# hcgs-servo-slam.net
KiCad netlist of a schematic drawn in EAGLE
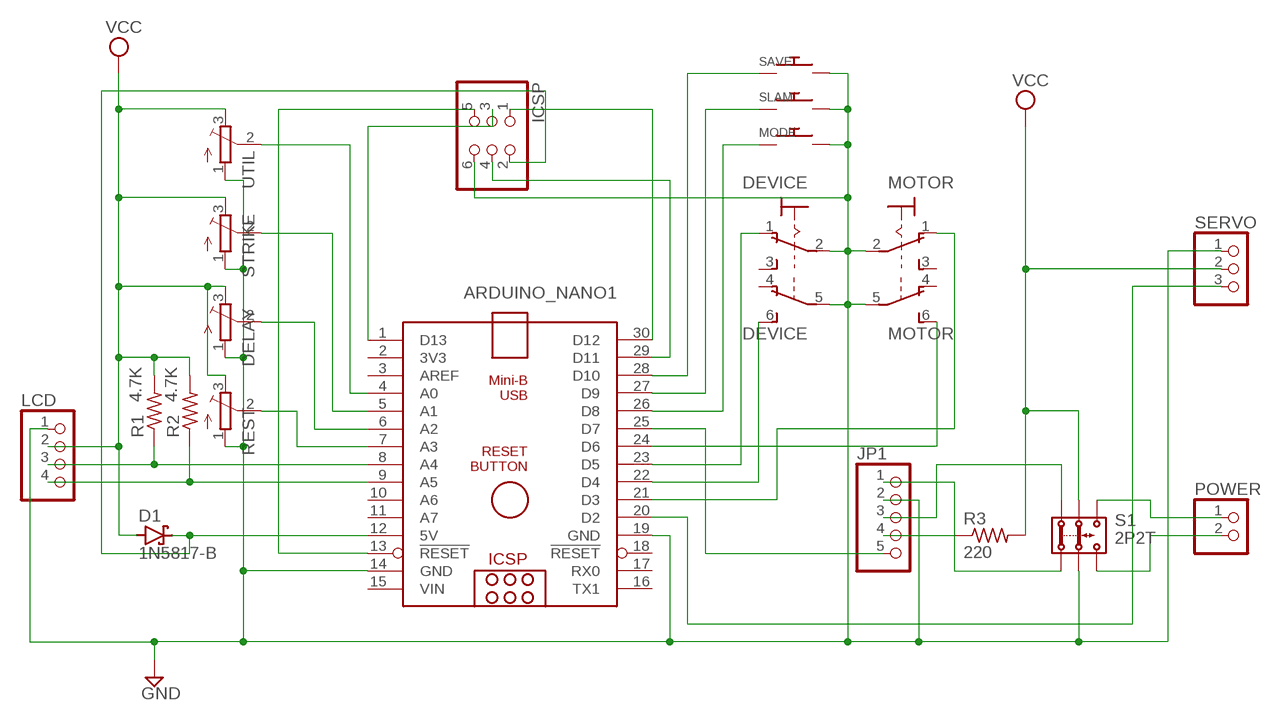
[diagram p0: schematic, sheet 1]

(export (version "E")
  (design (tool "Eeschema 10.0.6"))
  (components
    (comp (ref "ARDUINO_NANO1")
      (value "ARDUINO_NANO_HCARDUINO_NANO_NO_HOLE")
      (footprint "eagle-import:ARDUINO_NANO_NO_HOLE")
      (libsource (lib "eagle-import") (part "ARDUINO_NANO_HCARDUINO_NANO_NO_HOLE"))
    )
    (comp (ref "D1")
      (value "1N5817-B")
      (footprint "eagle-import:DO41-7.6")
      (libsource (lib "eagle-import") (part "1N5817-B"))
    )
    (comp (ref "DELAY")
      (value "TRIMPOT3386")
      (footprint "eagle-import:TRIM-3386")
      (libsource (lib "eagle-import") (part "TRIMPOT3386"))
    )
    (comp (ref "DEVICE")
      (value "320-938")
      (footprint "eagle-import:320-938")
      (libsource (lib "eagle-import") (part "320-938"))
    )
    (comp (ref "ICSP")
      (value "PINHD-2X3")
      (footprint "eagle-import:2X03")
      (libsource (lib "eagle-import") (part "PINHD-2X3"))
    )
    (comp (ref "JP1")
      (value "PINHD-1X5")
      (footprint "eagle-import:1X05")
      (libsource (lib "eagle-import") (part "PINHD-1X5"))
    )
    (comp (ref "LCD")
      (value "PINHD-1X4")
      (footprint "eagle-import:1X04")
      (libsource (lib "eagle-import") (part "PINHD-1X4"))
    )
    (comp (ref "MODE")
      (value "SWITCH_PUSHBUTTONEVQ-PE")
      (footprint "eagle-import:TACT_PANA-EVQ")
      (libsource (lib "eagle-import") (part "SWITCH_PUSHBUTTONEVQ-PE"))
    )
    (comp (ref "MOTOR")
      (value "320-938")
      (footprint "eagle-import:320-938")
      (libsource (lib "eagle-import") (part "320-938"))
    )
    (comp (ref "POWER")
      (value "PINHD-1X2")
      (footprint "eagle-import:1X02")
      (libsource (lib "eagle-import") (part "PINHD-1X2"))
    )
    (comp (ref "R1")
      (value "4.7K")
      (footprint "eagle-import:0309_12")
      (libsource (lib "eagle-import") (part "R-US_0309/12"))
    )
    (comp (ref "R2")
      (value "4.7K")
      (footprint "eagle-import:0309_12")
      (libsource (lib "eagle-import") (part "R-US_0309/12"))
    )
    (comp (ref "R3")
      (value "220")
      (footprint "eagle-import:0309_12")
      (libsource (lib "eagle-import") (part "R-US_0309/12"))
    )
    (comp (ref "REST")
      (value "TRIMPOT3386")
      (footprint "eagle-import:TRIM-3386")
      (libsource (lib "eagle-import") (part "TRIMPOT3386"))
    )
    (comp (ref "S1")
      (value "2P2T")
      (footprint "eagle-import:2P2T")
      (libsource (lib "eagle-import") (part "2P2T"))
    )
    (comp (ref "SAVE")
      (value "SWITCH_PUSHBUTTONEVQ-PE")
      (footprint "eagle-import:TACT_PANA-EVQ")
      (libsource (lib "eagle-import") (part "SWITCH_PUSHBUTTONEVQ-PE"))
    )
    (comp (ref "SERVO")
      (value "PINHD-1X3")
      (footprint "eagle-import:1X03")
      (libsource (lib "eagle-import") (part "PINHD-1X3"))
    )
    (comp (ref "SLAM")
      (value "SWITCH_PUSHBUTTONEVQ-PE")
      (footprint "eagle-import:TACT_PANA-EVQ")
      (libsource (lib "eagle-import") (part "SWITCH_PUSHBUTTONEVQ-PE"))
    )
    (comp (ref "STRIKE")
      (value "TRIMPOT3386")
      (footprint "eagle-import:TRIM-3386")
      (libsource (lib "eagle-import") (part "TRIMPOT3386"))
    )
    (comp (ref "UTIL")
      (value "TRIMPOT3386")
      (footprint "eagle-import:TRIM-3386")
      (libsource (lib "eagle-import") (part "TRIMPOT3386"))
    )
  )
  (nets
    (net (code "1") (name "/VIN") (class "Default")
      (node (ref "ARDUINO_NANO1") (pin "15") (pinfunction "VIN_15") (pintype "power_in"))
    )
    (net (code "2") (name "GND") (class "Default")
      (node (ref "ARDUINO_NANO1") (pin "14") (pinfunction "GND_14") (pintype "power_in"))
      (node (ref "ARDUINO_NANO1") (pin "19") (pinfunction "GND_19") (pintype "power_in"))
      (node (ref "DELAY") (pin "1") (pinfunction "A_1") (pintype "passive"))
      (node (ref "DEVICE") (pin "2") (pinfunction "P_2") (pintype "passive"))
      (node (ref "DEVICE") (pin "5") (pinfunction "P_5") (pintype "passive"))
      (node (ref "ICSP") (pin "6") (pinfunction "6_6") (pintype "passive"))
      (node (ref "JP1") (pin "2") (pinfunction "2_2") (pintype "passive"))
      (node (ref "LCD") (pin "1") (pinfunction "1_1") (pintype "passive"))
      (node (ref "MODE") (pin "P$2") (pinfunction "P$2_P$2") (pintype "passive"))
      (node (ref "MOTOR") (pin "2") (pinfunction "P_2") (pintype "passive"))
      (node (ref "MOTOR") (pin "5") (pinfunction "P_5") (pintype "passive"))
      (node (ref "REST") (pin "1") (pinfunction "A_1") (pintype "passive"))
      (node (ref "S1") (pin "2.2") (pinfunction "2.2_2.2") (pintype "passive"))
      (node (ref "SAVE") (pin "P$2") (pinfunction "P$2_P$2") (pintype "passive"))
      (node (ref "SERVO") (pin "1") (pinfunction "1_1") (pintype "passive"))
      (node (ref "SLAM") (pin "P$2") (pinfunction "P$2_P$2") (pintype "passive"))
      (node (ref "STRIKE") (pin "1") (pinfunction "A_1") (pintype "passive"))
      (node (ref "UTIL") (pin "1") (pinfunction "A_1") (pintype "passive"))
    )
    (net (code "3") (name "Net-(ARDUINO_NANO1-5V)") (class "Default")
      (node (ref "ARDUINO_NANO1") (pin "12") (pinfunction "5V_12") (pintype "power_in"))
      (node (ref "D1") (pin "C") (pinfunction "C_C") (pintype "passive"))
      (node (ref "ICSP") (pin "2") (pinfunction "2_2") (pintype "passive"))
    )
    (net (code "4") (name "Net-(ARDUINO_NANO1-A0)") (class "Default")
      (node (ref "ARDUINO_NANO1") (pin "4") (pinfunction "A0_4") (pintype "bidirectional"))
      (node (ref "UTIL") (pin "2") (pinfunction "S_2") (pintype "passive"))
    )
    (net (code "5") (name "Net-(ARDUINO_NANO1-A1)") (class "Default")
      (node (ref "ARDUINO_NANO1") (pin "5") (pinfunction "A1_5") (pintype "bidirectional"))
      (node (ref "STRIKE") (pin "2") (pinfunction "S_2") (pintype "passive"))
    )
    (net (code "6") (name "Net-(ARDUINO_NANO1-A2)") (class "Default")
      (node (ref "ARDUINO_NANO1") (pin "6") (pinfunction "A2_6") (pintype "bidirectional"))
      (node (ref "DELAY") (pin "2") (pinfunction "S_2") (pintype "passive"))
    )
    (net (code "7") (name "Net-(ARDUINO_NANO1-A3)") (class "Default")
      (node (ref "ARDUINO_NANO1") (pin "7") (pinfunction "A3_7") (pintype "bidirectional"))
      (node (ref "REST") (pin "2") (pinfunction "S_2") (pintype "passive"))
    )
    (net (code "8") (name "Net-(ARDUINO_NANO1-A4)") (class "Default")
      (node (ref "ARDUINO_NANO1") (pin "8") (pinfunction "A4_8") (pintype "bidirectional"))
      (node (ref "LCD") (pin "3") (pinfunction "3_3") (pintype "passive"))
      (node (ref "R1") (pin "1") (pinfunction "1_1") (pintype "passive"))
    )
    (net (code "9") (name "Net-(ARDUINO_NANO1-A5)") (class "Default")
      (node (ref "ARDUINO_NANO1") (pin "9") (pinfunction "A5_9") (pintype "bidirectional"))
      (node (ref "LCD") (pin "4") (pinfunction "4_4") (pintype "passive"))
      (node (ref "R2") (pin "1") (pinfunction "1_1") (pintype "passive"))
    )
    (net (code "10") (name "Net-(ARDUINO_NANO1-D2)") (class "Default")
      (node (ref "ARDUINO_NANO1") (pin "20") (pinfunction "D2_20") (pintype "bidirectional"))
      (node (ref "SERVO") (pin "3") (pinfunction "3_3") (pintype "passive"))
    )
    (net (code "11") (name "Net-(ARDUINO_NANO1-D3)") (class "Default")
      (node (ref "ARDUINO_NANO1") (pin "21") (pinfunction "D3_21") (pintype "bidirectional"))
      (node (ref "MOTOR") (pin "1") (pinfunction "O_1") (pintype "passive"))
    )
    (net (code "12") (name "Net-(ARDUINO_NANO1-D4)") (class "Default")
      (node (ref "ARDUINO_NANO1") (pin "22") (pinfunction "D4_22") (pintype "bidirectional"))
      (node (ref "DEVICE") (pin "6") (pinfunction "S_6") (pintype "passive"))
    )
    (net (code "13") (name "Net-(ARDUINO_NANO1-D5)") (class "Default")
      (node (ref "ARDUINO_NANO1") (pin "23") (pinfunction "D5_23") (pintype "bidirectional"))
      (node (ref "DEVICE") (pin "1") (pinfunction "O_1") (pintype "passive"))
    )
    (net (code "14") (name "Net-(ARDUINO_NANO1-D6)") (class "Default")
      (node (ref "ARDUINO_NANO1") (pin "24") (pinfunction "D6_24") (pintype "bidirectional"))
      (node (ref "MOTOR") (pin "6") (pinfunction "S_6") (pintype "passive"))
    )
    (net (code "15") (name "Net-(ARDUINO_NANO1-D7)") (class "Default")
      (node (ref "ARDUINO_NANO1") (pin "25") (pinfunction "D7_25") (pintype "bidirectional"))
      (node (ref "JP1") (pin "5") (pinfunction "5_5") (pintype "passive"))
    )
    (net (code "16") (name "Net-(ARDUINO_NANO1-D8)") (class "Default")
      (node (ref "ARDUINO_NANO1") (pin "26") (pinfunction "D8_26") (pintype "bidirectional"))
      (node (ref "MODE") (pin "P$1") (pinfunction "P$1_P$1") (pintype "passive"))
    )
    (net (code "17") (name "Net-(ARDUINO_NANO1-D9)") (class "Default")
      (node (ref "ARDUINO_NANO1") (pin "27") (pinfunction "D9_27") (pintype "bidirectional"))
      (node (ref "SLAM") (pin "P$1") (pinfunction "P$1_P$1") (pintype "passive"))
    )
    (net (code "18") (name "Net-(ARDUINO_NANO1-D10)") (class "Default")
      (node (ref "ARDUINO_NANO1") (pin "28") (pinfunction "D10_28") (pintype "bidirectional"))
      (node (ref "SAVE") (pin "P$1") (pinfunction "P$1_P$1") (pintype "passive"))
    )
    (net (code "19") (name "Net-(ARDUINO_NANO1-D11)") (class "Default")
      (node (ref "ARDUINO_NANO1") (pin "29") (pinfunction "D11_29") (pintype "bidirectional"))
      (node (ref "ICSP") (pin "4") (pinfunction "4_4") (pintype "passive"))
    )
    (net (code "20") (name "Net-(ARDUINO_NANO1-D12)") (class "Default")
      (node (ref "ARDUINO_NANO1") (pin "30") (pinfunction "D12_30") (pintype "bidirectional"))
      (node (ref "ICSP") (pin "1") (pinfunction "1_1") (pintype "passive"))
    )
    (net (code "21") (name "Net-(ARDUINO_NANO1-D13)") (class "Default")
      (node (ref "ARDUINO_NANO1") (pin "1") (pinfunction "D13_1") (pintype "bidirectional"))
      (node (ref "ICSP") (pin "3") (pinfunction "3_3") (pintype "passive"))
    )
    (net (code "22") (name "Net-(ARDUINO_NANO1-~{RESET}-Pad13)") (class "Default")
      (node (ref "ARDUINO_NANO1") (pin "13") (pinfunction "~{RESET}_13") (pintype "input"))
      (node (ref "ICSP") (pin "5") (pinfunction "5_5") (pintype "passive"))
    )
    (net (code "23") (name "Net-(JP1-Pad1)") (class "Default")
      (node (ref "JP1") (pin "1") (pinfunction "1_1") (pintype "passive"))
      (node (ref "S1") (pin "1.2") (pinfunction "1.2_1.2") (pintype "passive"))
    )
    (net (code "24") (name "Net-(JP1-Pad3)") (class "Default")
      (node (ref "JP1") (pin "3") (pinfunction "3_3") (pintype "passive"))
      (node (ref "S1") (pin "1.1") (pinfunction "1.1_1.1") (pintype "passive"))
    )
    (net (code "25") (name "Net-(JP1-Pad4)") (class "Default")
      (node (ref "JP1") (pin "4") (pinfunction "4_4") (pintype "passive"))
      (node (ref "R3") (pin "1") (pinfunction "1_1") (pintype "passive"))
    )
    (net (code "26") (name "Net-(POWER-Pad1)") (class "Default")
      (node (ref "POWER") (pin "1") (pinfunction "1_1") (pintype "passive"))
      (node (ref "S1") (pin "3.1") (pinfunction "3.1_3.1") (pintype "passive"))
    )
    (net (code "27") (name "Net-(POWER-Pad2)") (class "Default")
      (node (ref "POWER") (pin "2") (pinfunction "2_2") (pintype "passive"))
      (node (ref "S1") (pin "3.2") (pinfunction "3.2_3.2") (pintype "passive"))
    )
    (net (code "28") (name "VCC") (class "Default")
      (node (ref "D1") (pin "A") (pinfunction "A_A") (pintype "passive"))
      (node (ref "DELAY") (pin "3") (pinfunction "E_3") (pintype "passive"))
      (node (ref "LCD") (pin "2") (pinfunction "2_2") (pintype "passive"))
      (node (ref "R1") (pin "2") (pinfunction "2_2") (pintype "passive"))
      (node (ref "R2") (pin "2") (pinfunction "2_2") (pintype "passive"))
      (node (ref "R3") (pin "2") (pinfunction "2_2") (pintype "passive"))
      (node (ref "REST") (pin "3") (pinfunction "E_3") (pintype "passive"))
      (node (ref "S1") (pin "2.1") (pinfunction "2.1_2.1") (pintype "passive"))
      (node (ref "SERVO") (pin "2") (pinfunction "2_2") (pintype "passive"))
      (node (ref "STRIKE") (pin "3") (pinfunction "E_3") (pintype "passive"))
      (node (ref "UTIL") (pin "3") (pinfunction "E_3") (pintype "passive"))
    )
    (net (code "29") (name "unconnected-(ARDUINO_NANO1-3V3-Pad2)") (class "Default")
      (node (ref "ARDUINO_NANO1") (pin "2") (pinfunction "3V3_2") (pintype "output"))
    )
    (net (code "30") (name "unconnected-(ARDUINO_NANO1-A6-Pad10)") (class "Default")
      (node (ref "ARDUINO_NANO1") (pin "10") (pinfunction "A6_10") (pintype "bidirectional"))
    )
    (net (code "31") (name "unconnected-(ARDUINO_NANO1-A7-Pad11)") (class "Default")
      (node (ref "ARDUINO_NANO1") (pin "11") (pinfunction "A7_11") (pintype "bidirectional"))
    )
    (net (code "32") (name "unconnected-(ARDUINO_NANO1-AREF-Pad3)") (class "Default")
      (node (ref "ARDUINO_NANO1") (pin "3") (pinfunction "AREF_3") (pintype "input"))
    )
    (net (code "33") (name "unconnected-(ARDUINO_NANO1-RX0-Pad17)") (class "Default")
      (node (ref "ARDUINO_NANO1") (pin "17") (pinfunction "RX0_17") (pintype "bidirectional"))
    )
    (net (code "34") (name "unconnected-(ARDUINO_NANO1-TX1-Pad16)") (class "Default")
      (node (ref "ARDUINO_NANO1") (pin "16") (pinfunction "TX1_16") (pintype "bidirectional"))
    )
    (net (code "35") (name "unconnected-(ARDUINO_NANO1-~{RESET}-Pad18)") (class "Default")
      (node (ref "ARDUINO_NANO1") (pin "18") (pinfunction "~{RESET}_18") (pintype "input"))
    )
    (net (code "36") (name "unconnected-(DEVICEA-S-Pad3)") (class "Default")
      (node (ref "DEVICE") (pin "3") (pinfunction "S_3") (pintype "passive"))
    )
    (net (code "37") (name "unconnected-(DEVICEB-O-Pad4)") (class "Default")
      (node (ref "DEVICE") (pin "4") (pinfunction "O_4") (pintype "passive"))
    )
    (net (code "38") (name "unconnected-(MOTORA-S-Pad3)") (class "Default")
      (node (ref "MOTOR") (pin "3") (pinfunction "S_3") (pintype "passive"))
    )
    (net (code "39") (name "unconnected-(MOTORB-O-Pad4)") (class "Default")
      (node (ref "MOTOR") (pin "4") (pinfunction "O_4") (pintype "passive"))
    )
  )
)
